# KMO_IO_MV2_91.net
KiCad netlist of a schematic drawn in EAGLE
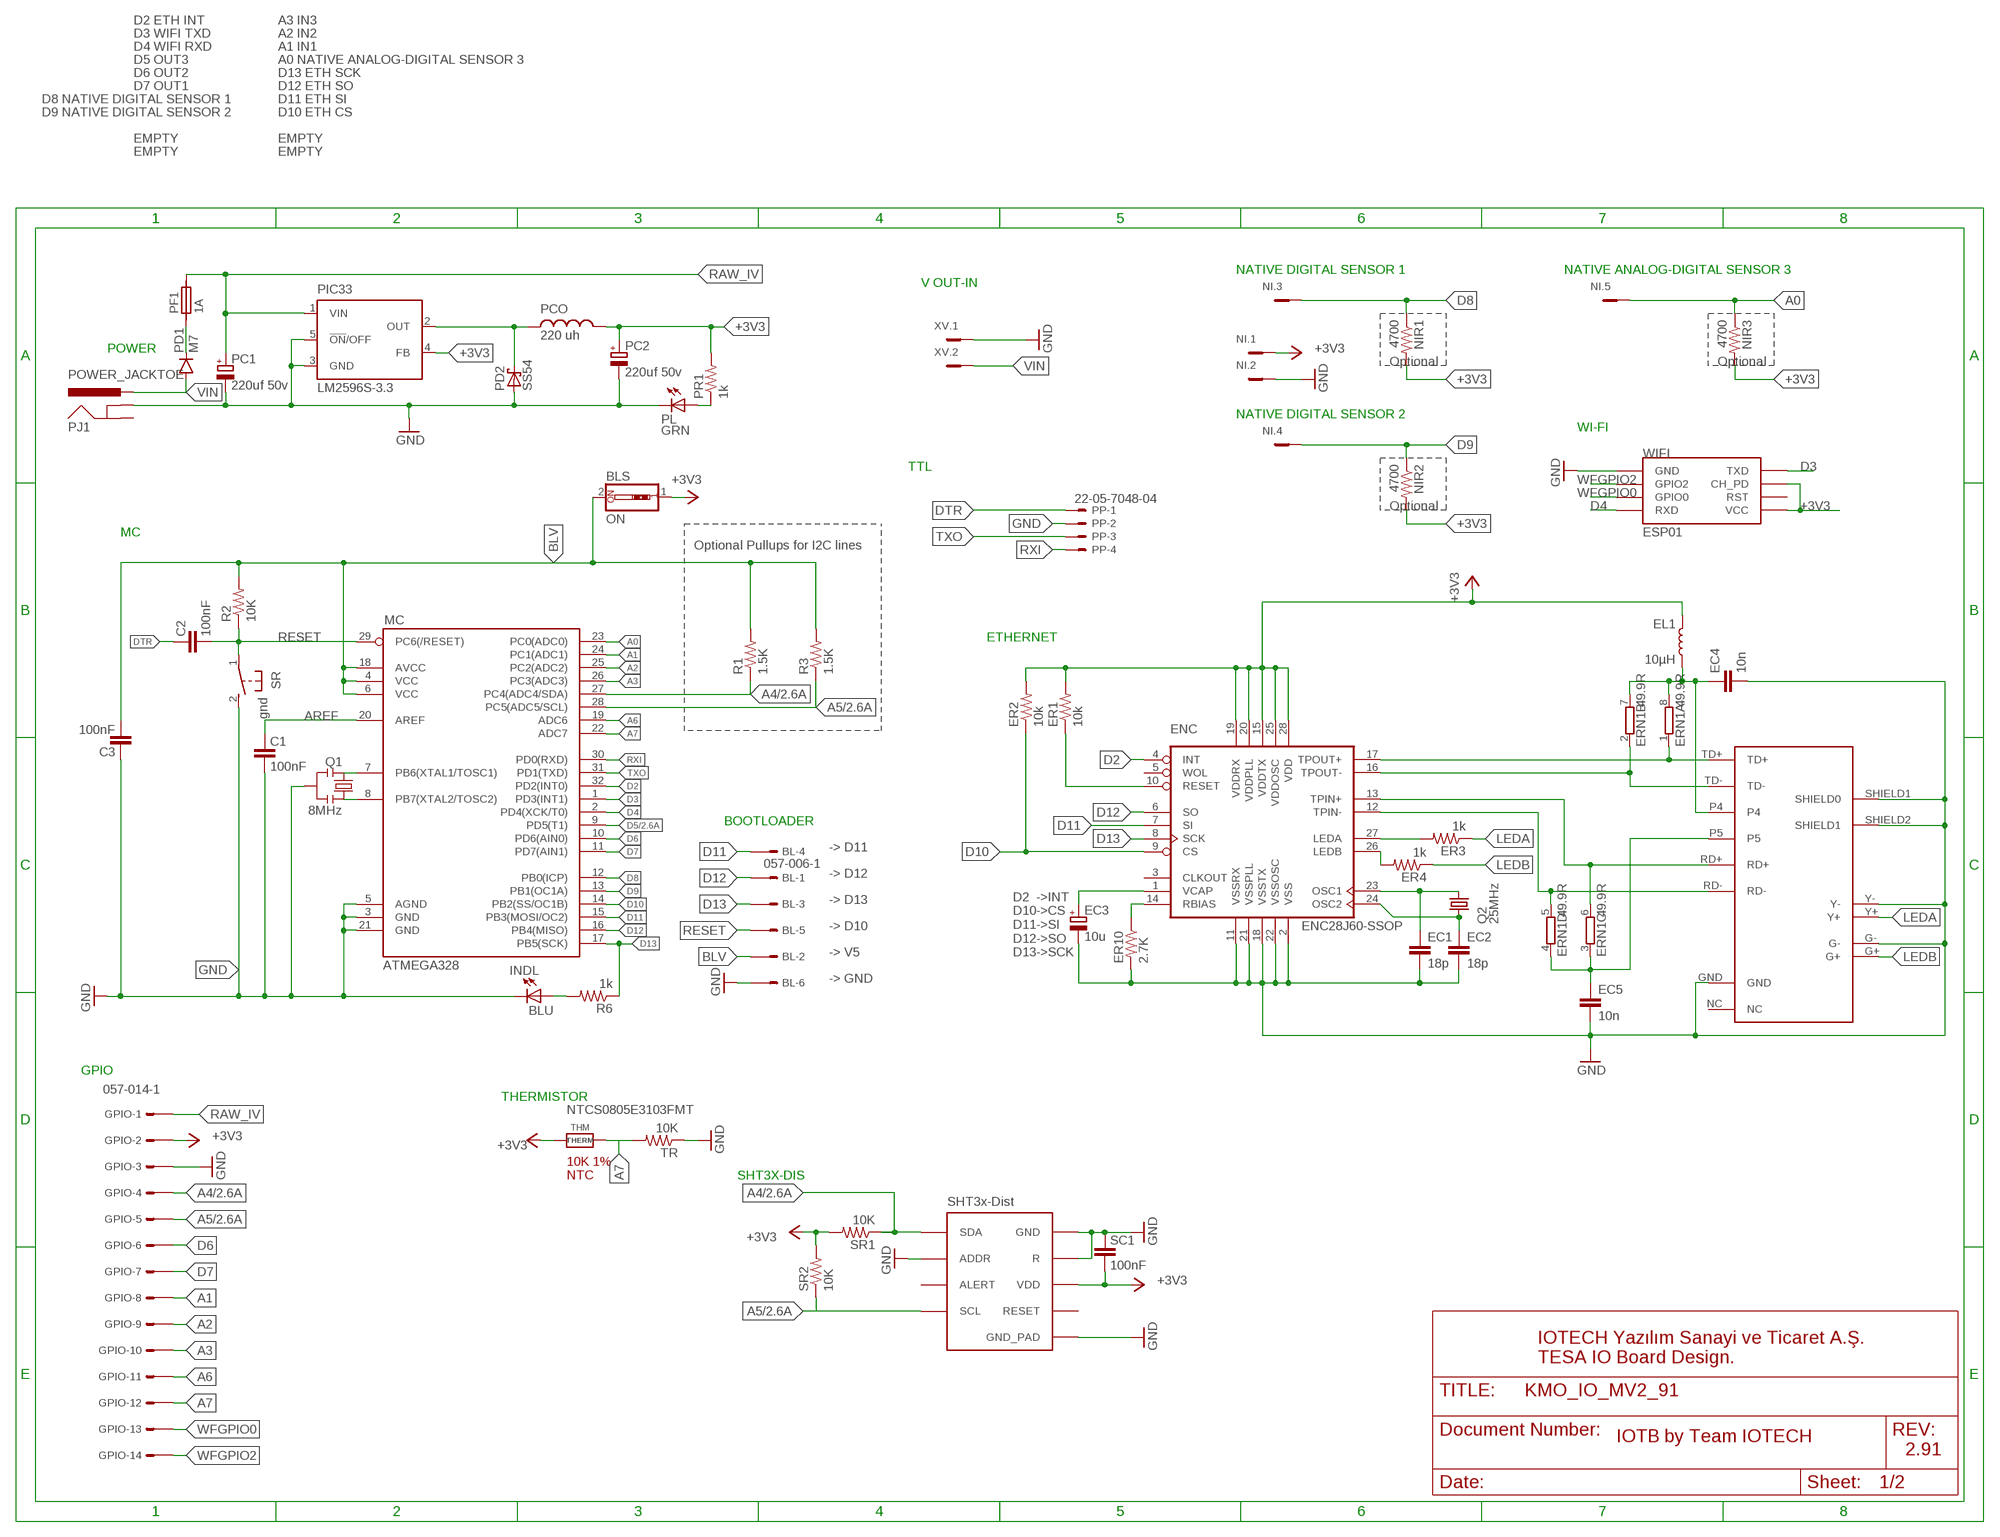
[diagram p0: schematic, sheet 1]
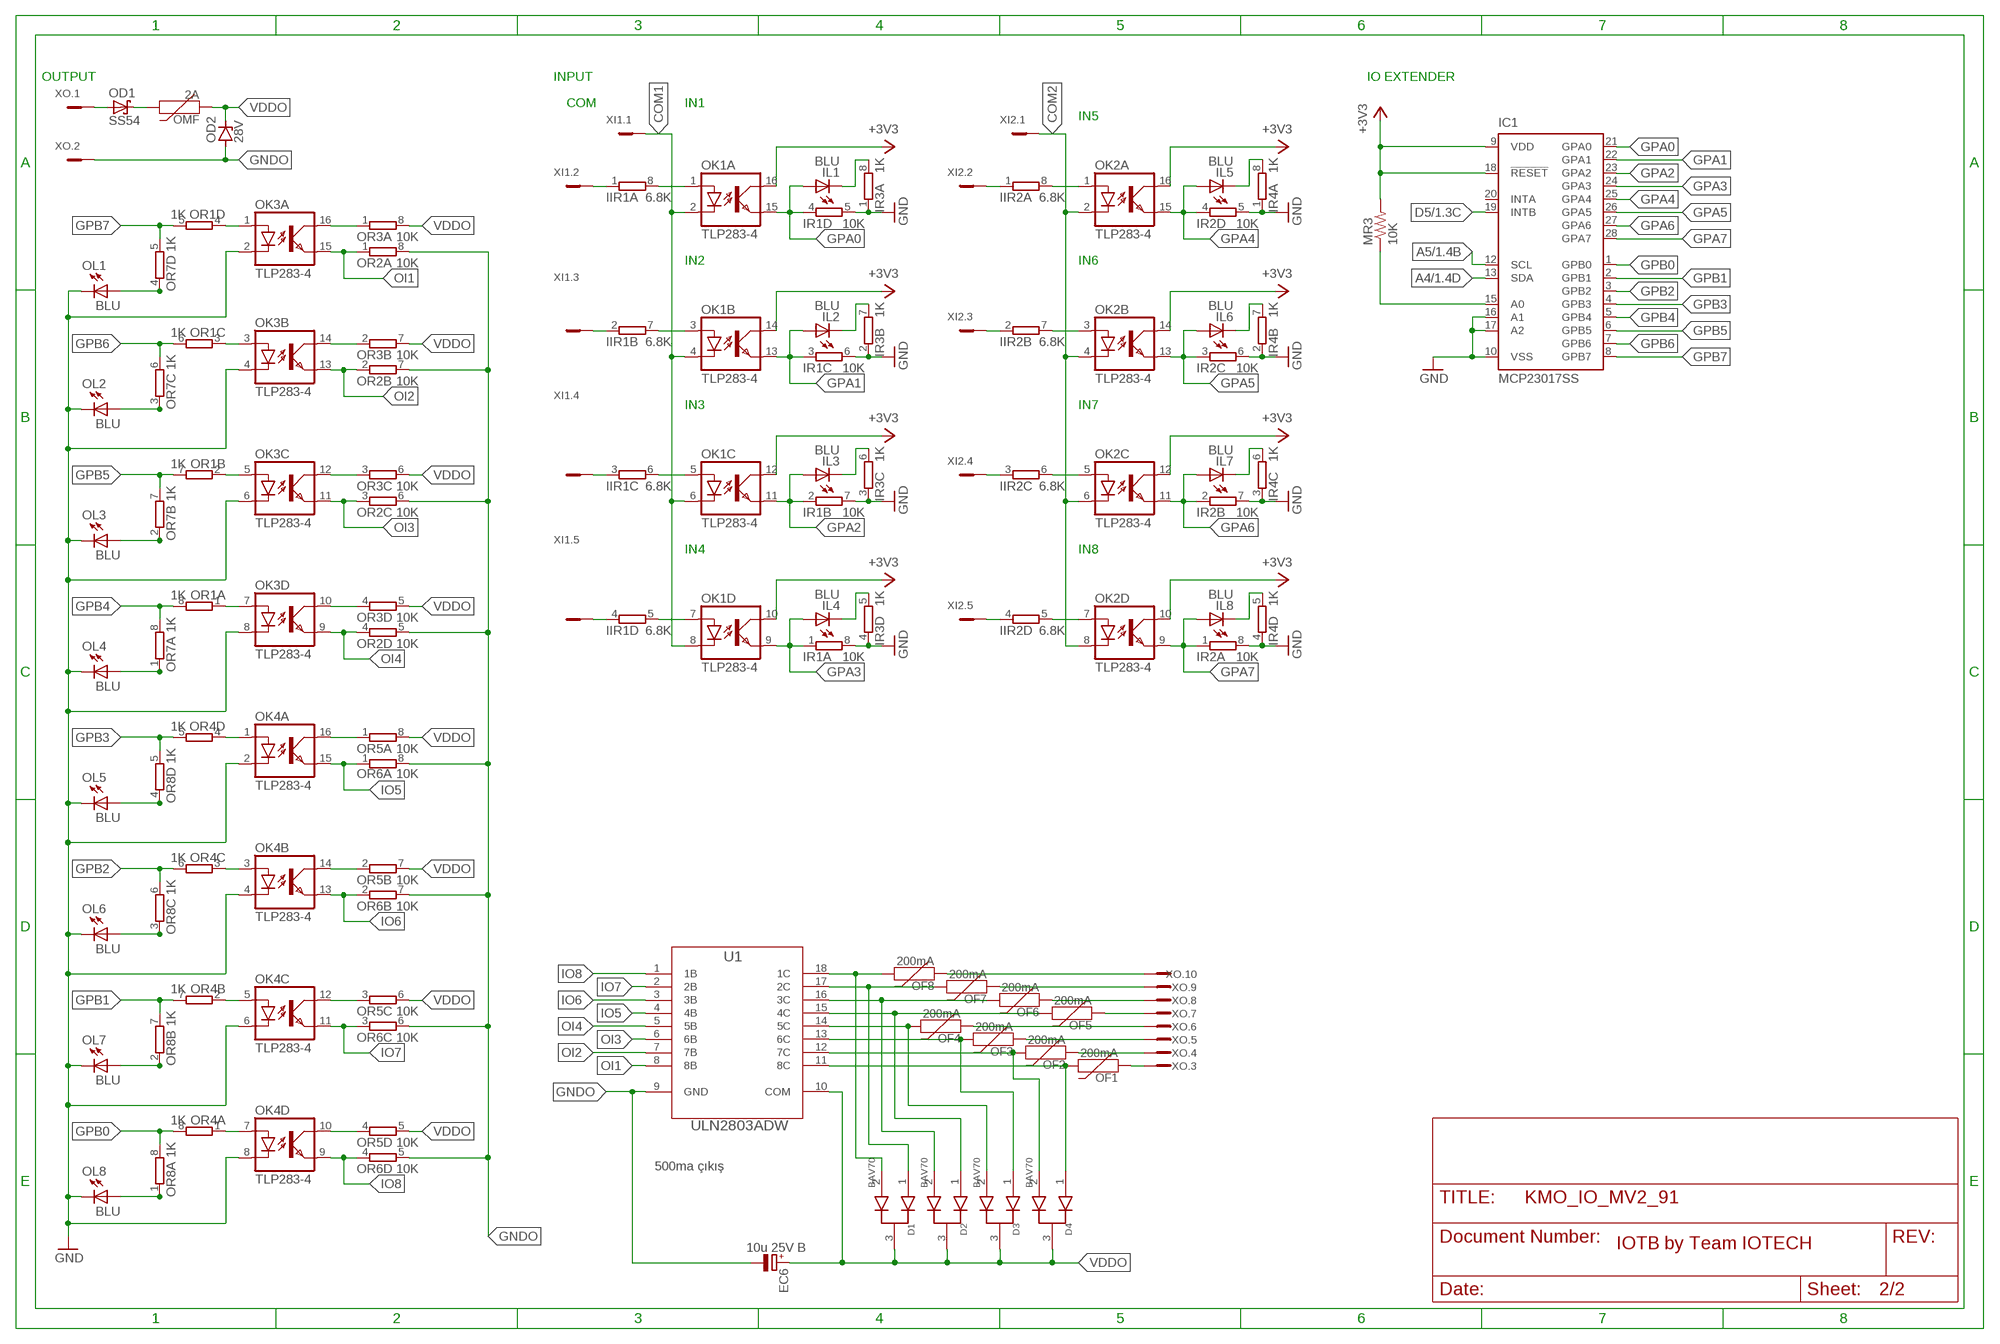
[diagram p1: schematic, sheet 2]

(export (version "E")
  (design (tool "Eeschema 10.0.6"))
  (components
    (comp (ref "D1")
      (value "BAV70")
      (footprint "eagle-import:SOT-23-3")
      (fields (field (name "MF") "Multicomp") (field (name "MP") "BAV70+"))
      (libsource (lib "eagle-import") (part "BAV70"))
    )
    (comp (ref "D2")
      (value "BAV70")
      (footprint "eagle-import:SOT-23-3")
      (fields (field (name "MF") "Multicomp") (field (name "MP") "BAV70+"))
      (libsource (lib "eagle-import") (part "BAV70"))
    )
    (comp (ref "D3")
      (value "BAV70")
      (footprint "eagle-import:SOT-23-3")
      (fields (field (name "MF") "Multicomp") (field (name "MP") "BAV70+"))
      (libsource (lib "eagle-import") (part "BAV70"))
    )
    (comp (ref "D4")
      (value "BAV70")
      (footprint "eagle-import:SOT-23-3")
      (fields (field (name "MF") "Multicomp") (field (name "MP") "BAV70+"))
      (libsource (lib "eagle-import") (part "BAV70"))
    )
    (comp (ref "EC6")
      (value "10u 25V B")
      (footprint "eagle-import:SMC_B")
      (libsource (lib "eagle-import") (part "CPOL-EUSMCB"))
    )
    (comp (ref "IC1")
      (value "MCP23017SS")
      (footprint "eagle-import:SSOP28")
      (fields (field (name "MF") "MICROCHIP") (field (name "MPN") "MCP23017-E/SS"))
      (libsource (lib "eagle-import") (part "MCP23017SS"))
    )
    (comp (ref "IIR1")
      (value "6.8K")
      (footprint "eagle-import:0603-ARV")
      (libsource (lib "eagle-import") (part "4R-N0603-ARV"))
    )
    (comp (ref "IIR2")
      (value "6.8K")
      (footprint "eagle-import:0603-ARV")
      (libsource (lib "eagle-import") (part "4R-N0603-ARV"))
    )
    (comp (ref "IL1")
      (value "BLU")
      (footprint "eagle-import:CHIP-LED0805")
      (libsource (lib "eagle-import") (part "LEDCHIP-LED0805"))
    )
    (comp (ref "IL2")
      (value "BLU")
      (footprint "eagle-import:CHIP-LED0805")
      (libsource (lib "eagle-import") (part "LEDCHIP-LED0805"))
    )
    (comp (ref "IL3")
      (value "BLU")
      (footprint "eagle-import:CHIP-LED0805")
      (libsource (lib "eagle-import") (part "LEDCHIP-LED0805"))
    )
    (comp (ref "IL4")
      (value "BLU")
      (footprint "eagle-import:CHIP-LED0805")
      (libsource (lib "eagle-import") (part "LEDCHIP-LED0805"))
    )
    (comp (ref "IL5")
      (value "BLU")
      (footprint "eagle-import:CHIP-LED0805")
      (libsource (lib "eagle-import") (part "LEDCHIP-LED0805"))
    )
    (comp (ref "IL6")
      (value "BLU")
      (footprint "eagle-import:CHIP-LED0805")
      (libsource (lib "eagle-import") (part "LEDCHIP-LED0805"))
    )
    (comp (ref "IL7")
      (value "BLU")
      (footprint "eagle-import:CHIP-LED0805")
      (libsource (lib "eagle-import") (part "LEDCHIP-LED0805"))
    )
    (comp (ref "IL8")
      (value "BLU")
      (footprint "eagle-import:CHIP-LED0805")
      (libsource (lib "eagle-import") (part "LEDCHIP-LED0805"))
    )
    (comp (ref "IR1")
      (value "10K")
      (footprint "eagle-import:0603-ARV")
      (libsource (lib "eagle-import") (part "4R-N0603-ARV"))
    )
    (comp (ref "IR2")
      (value "10K")
      (footprint "eagle-import:0603-ARV")
      (libsource (lib "eagle-import") (part "4R-N0603-ARV"))
    )
    (comp (ref "IR3")
      (value "1K")
      (footprint "eagle-import:0603-ARV")
      (libsource (lib "eagle-import") (part "4R-N0603-ARV"))
    )
    (comp (ref "IR4")
      (value "1K")
      (footprint "eagle-import:0603-ARV")
      (libsource (lib "eagle-import") (part "4R-N0603-ARV"))
    )
    (comp (ref "MR3")
      (value "10K")
      (footprint "eagle-import:0805")
      (libsource (lib "eagle-import") (part "RESISTOR0805-RES"))
    )
    (comp (ref "OD1")
      (value "SS54")
      (footprint "eagle-import:SMB")
      (libsource (lib "eagle-import") (part "SCHOTTKY-DIODESMD"))
    )
    (comp (ref "OD2")
      (value "28V")
      (footprint "eagle-import:SMB")
      (libsource (lib "eagle-import") (part "ZENER-DIODESMB"))
    )
    (comp (ref "OF1")
      (value "200mA")
      (footprint "eagle-import:1206")
      (libsource (lib "eagle-import") (part "PPTC_0.75A"))
    )
    (comp (ref "OF2")
      (value "200mA")
      (footprint "eagle-import:1206")
      (libsource (lib "eagle-import") (part "PPTC_0.75A"))
    )
    (comp (ref "OF3")
      (value "200mA")
      (footprint "eagle-import:1206")
      (libsource (lib "eagle-import") (part "PPTC_0.75A"))
    )
    (comp (ref "OF4")
      (value "200mA")
      (footprint "eagle-import:1206")
      (libsource (lib "eagle-import") (part "PPTC_0.75A"))
    )
    (comp (ref "OF5")
      (value "200mA")
      (footprint "eagle-import:1206")
      (libsource (lib "eagle-import") (part "PPTC_0.75A"))
    )
    (comp (ref "OF6")
      (value "200mA")
      (footprint "eagle-import:1206")
      (libsource (lib "eagle-import") (part "PPTC_0.75A"))
    )
    (comp (ref "OF7")
      (value "200mA")
      (footprint "eagle-import:1206")
      (libsource (lib "eagle-import") (part "PPTC_0.75A"))
    )
    (comp (ref "OF8")
      (value "200mA")
      (footprint "eagle-import:1206")
      (libsource (lib "eagle-import") (part "PPTC_0.75A"))
    )
    (comp (ref "OK1")
      (value "TLP283-4")
      (footprint "eagle-import:MINI-FLAT-16")
      (fields (field (name "SPICEPREFIX") "O"))
      (libsource (lib "eagle-import") (part "TLP283-4"))
    )
    (comp (ref "OK2")
      (value "TLP283-4")
      (footprint "eagle-import:MINI-FLAT-16")
      (fields (field (name "SPICEPREFIX") "O"))
      (libsource (lib "eagle-import") (part "TLP283-4"))
    )
    (comp (ref "OK3")
      (value "TLP283-4")
      (footprint "eagle-import:MINI-FLAT-16")
      (libsource (lib "eagle-import") (part "TLP283-4"))
    )
    (comp (ref "OK4")
      (value "TLP283-4")
      (footprint "eagle-import:MINI-FLAT-16")
      (libsource (lib "eagle-import") (part "TLP283-4"))
    )
    (comp (ref "OL1")
      (value "BLU")
      (footprint "eagle-import:CHIP-LED0805")
      (libsource (lib "eagle-import") (part "LEDCHIP-LED0805"))
    )
    (comp (ref "OL2")
      (value "BLU")
      (footprint "eagle-import:CHIP-LED0805")
      (libsource (lib "eagle-import") (part "LEDCHIP-LED0805"))
    )
    (comp (ref "OL3")
      (value "BLU")
      (footprint "eagle-import:CHIP-LED0805")
      (libsource (lib "eagle-import") (part "LEDCHIP-LED0805"))
    )
    (comp (ref "OL4")
      (value "BLU")
      (footprint "eagle-import:CHIP-LED0805")
      (libsource (lib "eagle-import") (part "LEDCHIP-LED0805"))
    )
    (comp (ref "OL5")
      (value "BLU")
      (footprint "eagle-import:CHIP-LED0805")
      (libsource (lib "eagle-import") (part "LEDCHIP-LED0805"))
    )
    (comp (ref "OL6")
      (value "BLU")
      (footprint "eagle-import:CHIP-LED0805")
      (libsource (lib "eagle-import") (part "LEDCHIP-LED0805"))
    )
    (comp (ref "OL7")
      (value "BLU")
      (footprint "eagle-import:CHIP-LED0805")
      (libsource (lib "eagle-import") (part "LEDCHIP-LED0805"))
    )
    (comp (ref "OL8")
      (value "BLU")
      (footprint "eagle-import:CHIP-LED0805")
      (libsource (lib "eagle-import") (part "LEDCHIP-LED0805"))
    )
    (comp (ref "OMF")
      (value "2A")
      (footprint "eagle-import:1206")
      (libsource (lib "eagle-import") (part "PPTC_0.75A"))
    )
    (comp (ref "OR1")
      (value "1K")
      (footprint "eagle-import:0603-ARV")
      (libsource (lib "eagle-import") (part "4R-N0603-ARV"))
    )
    (comp (ref "OR2")
      (value "10K")
      (footprint "eagle-import:0603-ARV")
      (libsource (lib "eagle-import") (part "4R-N0603-ARV"))
    )
    (comp (ref "OR3")
      (value "10K")
      (footprint "eagle-import:0603-ARV")
      (libsource (lib "eagle-import") (part "4R-N0603-ARV"))
    )
    (comp (ref "OR4")
      (value "1K")
      (footprint "eagle-import:0603-ARV")
      (libsource (lib "eagle-import") (part "4R-N0603-ARV"))
    )
    (comp (ref "OR5")
      (value "10K")
      (footprint "eagle-import:0603-ARV")
      (libsource (lib "eagle-import") (part "4R-N0603-ARV"))
    )
    (comp (ref "OR6")
      (value "10K")
      (footprint "eagle-import:0603-ARV")
      (libsource (lib "eagle-import") (part "4R-N0603-ARV"))
    )
    (comp (ref "OR7")
      (value "1K")
      (footprint "eagle-import:0603-ARV")
      (libsource (lib "eagle-import") (part "4R-N0603-ARV"))
    )
    (comp (ref "OR8")
      (value "1K")
      (footprint "eagle-import:0603-ARV")
      (libsource (lib "eagle-import") (part "4R-N0603-ARV"))
    )
    (comp (ref "U1")
      (value "ULN2803ADW")
      (footprint "eagle-import:SOIC127P1030X265-18N")
      (libsource (lib "eagle-import") (part "ULN2803ADW"))
    )
    (comp (ref "XI1")
      (value "MC5")
      (footprint "eagle-import:MC5")
      (libsource (lib "eagle-import") (part "MC5"))
    )
    (comp (ref "XI2")
      (value "MC5")
      (footprint "eagle-import:MC5")
      (libsource (lib "eagle-import") (part "MC5"))
    )
    (comp (ref "XO")
      (value "MC10")
      (footprint "eagle-import:MC10")
      (libsource (lib "eagle-import") (part "MC10"))
    )
    (comp (ref "BL")
      (value "057-006-1")
      (footprint "eagle-import:057-006-1")
      (libsource (lib "eagle-import") (part "057-006-1"))
    )
    (comp (ref "BLS")
      (value "ON")
      (footprint "eagle-import:EDG-01")
      (libsource (lib "eagle-import") (part "SW_DIP-1"))
    )
    (comp (ref "C1")
      (value "100nF")
      (footprint "eagle-import:0805")
      (libsource (lib "eagle-import") (part "CAP0805"))
    )
    (comp (ref "C2")
      (value "100nF")
      (footprint "eagle-import:0805")
      (libsource (lib "eagle-import") (part "CAP0805"))
    )
    (comp (ref "C3")
      (value "100nF")
      (footprint "eagle-import:0805")
      (libsource (lib "eagle-import") (part "CAP0805"))
    )
    (comp (ref "EC1")
      (value "18p")
      (footprint "eagle-import:0805")
      (libsource (lib "eagle-import") (part "CAP0805"))
    )
    (comp (ref "EC2")
      (value "18p")
      (footprint "eagle-import:0805")
      (libsource (lib "eagle-import") (part "CAP0805"))
    )
    (comp (ref "EC3")
      (value "10u")
      (footprint "eagle-import:CT3216")
      (libsource (lib "eagle-import") (part "CPOL-EUCT3216"))
    )
    (comp (ref "EC4")
      (value "10n")
      (footprint "eagle-import:0805")
      (libsource (lib "eagle-import") (part "CAP0805"))
    )
    (comp (ref "EC5")
      (value "10n")
      (footprint "eagle-import:0805")
      (libsource (lib "eagle-import") (part "CAP0805"))
    )
    (comp (ref "EL1")
      (value "10µH")
      (footprint "eagle-import:0805")
      (libsource (lib "eagle-import") (part "INDUCTOR-0805-3.3UH"))
    )
    (comp (ref "ENC")
      (value "ENC28J60-SSOP")
      (footprint "eagle-import:SSOP28")
      (libsource (lib "eagle-import") (part "ENC28J60-SSOP"))
    )
    (comp (ref "ER1")
      (value "10k")
      (footprint "eagle-import:0805")
      (libsource (lib "eagle-import") (part "RESISTOR0805-RES"))
    )
    (comp (ref "ER2")
      (value "10k")
      (footprint "eagle-import:0805")
      (libsource (lib "eagle-import") (part "RESISTOR0805-RES"))
    )
    (comp (ref "ER3")
      (value "1k")
      (footprint "eagle-import:0805")
      (libsource (lib "eagle-import") (part "RESISTOR0805-RES"))
    )
    (comp (ref "ER4")
      (value "1k")
      (footprint "eagle-import:0805")
      (libsource (lib "eagle-import") (part "RESISTOR0805-RES"))
    )
    (comp (ref "ER10")
      (value "2.7K")
      (footprint "eagle-import:0805")
      (libsource (lib "eagle-import") (part "RESISTOR0805-RES"))
    )
    (comp (ref "ERN1")
      (value "49.9R")
      (footprint "eagle-import:0603-ARV")
      (libsource (lib "eagle-import") (part "4R-N0603-ARV"))
    )
    (comp (ref "GPIO")
      (value "057-014-1")
      (footprint "eagle-import:057-014-1")
      (libsource (lib "eagle-import") (part "057-014-1"))
    )
    (comp (ref "INDL")
      (value "BLU")
      (footprint "eagle-import:CHIP-LED0805")
      (libsource (lib "eagle-import") (part "LEDCHIP-LED0805"))
    )
    (comp (ref "MC")
      (value "ATMEGA328")
      (footprint "eagle-import:TQFP32-08")
      (libsource (lib "eagle-import") (part "ATMEGA168"))
    )
    (comp (ref "NI")
      (value "MC5")
      (footprint "eagle-import:MC5")
      (libsource (lib "eagle-import") (part "MC5"))
    )
    (comp (ref "NIR1")
      (value "4700")
      (footprint "eagle-import:0805")
      (libsource (lib "eagle-import") (part "RESISTOR0805-RES"))
    )
    (comp (ref "NIR2")
      (value "4700")
      (footprint "eagle-import:0805")
      (libsource (lib "eagle-import") (part "RESISTOR0805-RES"))
    )
    (comp (ref "NIR3")
      (value "4700")
      (footprint "eagle-import:0805")
      (libsource (lib "eagle-import") (part "RESISTOR0805-RES"))
    )
    (comp (ref "PC1")
      (value "220uf 50v")
      (footprint "eagle-import:140CLH-1010")
      (libsource (lib "eagle-import") (part "CPOL-EU140CLH-1010"))
    )
    (comp (ref "PC2")
      (value "220uf 50v")
      (footprint "eagle-import:140CLH-1010")
      (libsource (lib "eagle-import") (part "CPOL-EU140CLH-1010"))
    )
    (comp (ref "PCO")
      (value "220 uh")
      (footprint "eagle-import:MSS1260")
      (libsource (lib "eagle-import") (part "MSS1260"))
    )
    (comp (ref "PD1")
      (value "M7")
      (footprint "eagle-import:SMA-DIODE")
      (libsource (lib "eagle-import") (part "DIODESMA"))
    )
    (comp (ref "PD2")
      (value "SS54")
      (footprint "eagle-import:SMB")
      (libsource (lib "eagle-import") (part "SCHOTTKY-DIODESMD"))
    )
    (comp (ref "PF1")
      (value "1A")
      (footprint "eagle-import:1820")
      (libsource (lib "eagle-import") (part "SIBA194600"))
    )
    (comp (ref "PIC33")
      (value "LM2596S-3.3")
      (footprint "eagle-import:TO263-5")
      (fields
        (field (name "MF") "NATIONAL SEMICONDUCTOR")
        (field (name "MPN") "LM2596S-ADJ/NOPB")
        (field (name "SPICEPREFIX") "X")
      )
      (libsource (lib "eagle-import") (part "LM2596S"))
    )
    (comp (ref "PJ1")
      (value "POWER_JACKTOE")
      (footprint "eagle-import:POWER_JACK_SMD_OVERPASTE_TOE")
      (libsource (lib "eagle-import") (part "POWER_JACKTOE"))
    )
    (comp (ref "PL")
      (value "GRN")
      (footprint "eagle-import:CHIP-LED0805")
      (libsource (lib "eagle-import") (part "LEDCHIP-LED0805"))
    )
    (comp (ref "PP")
      (value "22-05-7048-04")
      (footprint "eagle-import:7395-04")
      (fields (field (name "MF") "MOLEX"))
      (libsource (lib "eagle-import") (part "22-?-0405-7048"))
    )
    (comp (ref "PR1")
      (value "1k")
      (footprint "eagle-import:0805")
      (libsource (lib "eagle-import") (part "RESISTOR0805-RES"))
    )
    (comp (ref "Q1")
      (value "8MHz")
      (footprint "eagle-import:RESONATOR-SMD-1_1")
      (libsource (lib "eagle-import") (part "RESONATOR1{colon}1"))
    )
    (comp (ref "Q2")
      (value "25MHz")
      (footprint "eagle-import:5.0X3.2_2")
      (libsource (lib "eagle-import") (part "KX-9B"))
    )
    (comp (ref "R1")
      (value "1.5K")
      (footprint "eagle-import:0805")
      (libsource (lib "eagle-import") (part "RESISTOR0805-RES"))
    )
    (comp (ref "R2")
      (value "10K")
      (footprint "eagle-import:0805")
      (libsource (lib "eagle-import") (part "RESISTOR0805-RES"))
    )
    (comp (ref "R3")
      (value "1.5K")
      (footprint "eagle-import:0805")
      (libsource (lib "eagle-import") (part "RESISTOR0805-RES"))
    )
    (comp (ref "R6")
      (value "1k")
      (footprint "eagle-import:0805")
      (libsource (lib "eagle-import") (part "RESISTOR0805-RES"))
    )
    (comp (ref "SC1")
      (value "100nF")
      (footprint "eagle-import:0805")
      (libsource (lib "eagle-import") (part "CAP0805"))
    )
    (comp (ref "SHT")
      (value "SHT3X")
      (footprint "eagle-import:SHT3X")
      (libsource (lib "eagle-import") (part "SHT3X"))
    )
    (comp (ref "SR")
      (value "gnd")
      (footprint "eagle-import:B3F-31XX")
      (fields (field (name "MPN") "B3F-3100"))
      (libsource (lib "eagle-import") (part "31-XX"))
    )
    (comp (ref "SR1")
      (value "10K")
      (footprint "eagle-import:0805")
      (libsource (lib "eagle-import") (part "RESISTOR0805-RES"))
    )
    (comp (ref "SR2")
      (value "10K")
      (footprint "eagle-import:0805")
      (libsource (lib "eagle-import") (part "RESISTOR0805-RES"))
    )
    (comp (ref "THM")
      (value "THERM")
      (footprint "eagle-import:MICROBUILDER_0805_NOTHERMALS")
      (libsource (lib "eagle-import") (part "MICROBUILDER_RESISTOR0805_NOTHERMALS"))
    )
    (comp (ref "TR")
      (value "10K")
      (footprint "eagle-import:0805")
      (libsource (lib "eagle-import") (part "RESISTOR0805-RES"))
    )
    (comp (ref "U$2")
      (value "HR911105A")
      (footprint "eagle-import:RJ45")
      (libsource (lib "eagle-import") (part "HR911105A"))
    )
    (comp (ref "WIFI")
      (value "ESP01")
      (footprint "eagle-import:ESP01")
      (libsource (lib "eagle-import") (part "ESP01"))
    )
    (comp (ref "XV")
      (value "MC2")
      (footprint "eagle-import:MC2")
      (libsource (lib "eagle-import") (part "MC2"))
    )
  )
  (nets
    (net (code "1") (name "+3V3") (class "Default")
      (node (ref "BLS") (pin "1") (pinfunction "1_1") (pintype "passive"))
      (node (ref "EL1") (pin "1") (pinfunction "1_1") (pintype "passive"))
      (node (ref "ENC") (pin "15") (pinfunction "VDDTX_15") (pintype "power_in"))
      (node (ref "ENC") (pin "19") (pinfunction "VDDRX_19") (pintype "power_in"))
      (node (ref "ENC") (pin "20") (pinfunction "VDDPLL_20") (pintype "power_in"))
      (node (ref "ENC") (pin "25") (pinfunction "VDDOSC_25") (pintype "power_in"))
      (node (ref "ENC") (pin "28") (pinfunction "VDD_28") (pintype "power_in"))
      (node (ref "ER1") (pin "2") (pinfunction "2_2") (pintype "passive"))
      (node (ref "ER2") (pin "2") (pinfunction "2_2") (pintype "passive"))
      (node (ref "GPIO") (pin "2") (pinfunction "S_2") (pintype "passive"))
      (node (ref "IC1") (pin "18") (pinfunction "~{RESET}_18") (pintype "input"))
      (node (ref "IC1") (pin "9") (pinfunction "VDD_9") (pintype "power_in"))
      (node (ref "MR3") (pin "2") (pinfunction "2_2") (pintype "passive"))
      (node (ref "NI") (pin "1") (pinfunction "SK_1") (pintype "passive"))
      (node (ref "NIR1") (pin "2") (pinfunction "2_2") (pintype "passive"))
      (node (ref "NIR2") (pin "2") (pinfunction "2_2") (pintype "passive"))
      (node (ref "NIR3") (pin "2") (pinfunction "2_2") (pintype "passive"))
      (node (ref "OK1") (pin "10") (pinfunction "COL_10") (pintype "passive"))
      (node (ref "OK1") (pin "12") (pinfunction "COL_12") (pintype "passive"))
      (node (ref "OK1") (pin "14") (pinfunction "COL_14") (pintype "passive"))
      (node (ref "OK1") (pin "16") (pinfunction "COL_16") (pintype "passive"))
      (node (ref "OK2") (pin "10") (pinfunction "COL_10") (pintype "passive"))
      (node (ref "OK2") (pin "12") (pinfunction "COL_12") (pintype "passive"))
      (node (ref "OK2") (pin "14") (pinfunction "COL_14") (pintype "passive"))
      (node (ref "OK2") (pin "16") (pinfunction "COL_16") (pintype "passive"))
      (node (ref "PC2") (pin "+") (pinfunction "+_+") (pintype "passive"))
      (node (ref "PCO") (pin "P$1") (pinfunction "P$1_P$1") (pintype "passive"))
      (node (ref "PIC33") (pin "4") (pinfunction "FB_4") (pintype "input"))
      (node (ref "PR1") (pin "2") (pinfunction "2_2") (pintype "passive"))
      (node (ref "SC1") (pin "1") (pinfunction "1_1") (pintype "passive"))
      (node (ref "SHT") (pin "VDD") (pinfunction "VDD_VDD") (pintype "bidirectional"))
      (node (ref "SR1") (pin "2") (pinfunction "2_2") (pintype "passive"))
      (node (ref "SR2") (pin "2") (pinfunction "2_2") (pintype "passive"))
      (node (ref "THM") (pin "1") (pinfunction "1_1") (pintype "passive"))
      (node (ref "WIFI") (pin "CH_PD") (pinfunction "CH_PD_CH_PD") (pintype "bidirectional"))
      (node (ref "WIFI") (pin "VCC") (pinfunction "VCC_VCC") (pintype "bidirectional"))
    )
    (net (code "2") (name "A0") (class "Default")
      (node (ref "MC") (pin "23") (pinfunction "PC0(ADC0)_23") (pintype "bidirectional"))
      (node (ref "NI") (pin "5") (pinfunction "SK_5") (pintype "passive"))
      (node (ref "NIR3") (pin "1") (pinfunction "1_1") (pintype "passive"))
    )
    (net (code "3") (name "A1") (class "Default")
      (node (ref "GPIO") (pin "8") (pinfunction "S_8") (pintype "passive"))
      (node (ref "MC") (pin "24") (pinfunction "PC1(ADC1)_24") (pintype "bidirectional"))
    )
    (net (code "4") (name "A2") (class "Default")
      (node (ref "GPIO") (pin "9") (pinfunction "S_9") (pintype "passive"))
      (node (ref "MC") (pin "25") (pinfunction "PC2(ADC2)_25") (pintype "bidirectional"))
    )
    (net (code "5") (name "A3") (class "Default")
      (node (ref "GPIO") (pin "10") (pinfunction "S_10") (pintype "passive"))
      (node (ref "MC") (pin "26") (pinfunction "PC3(ADC3)_26") (pintype "bidirectional"))
    )
    (net (code "6") (name "A4") (class "Default")
      (node (ref "GPIO") (pin "4") (pinfunction "S_4") (pintype "passive"))
      (node (ref "IC1") (pin "13") (pinfunction "SDA_13") (pintype "bidirectional"))
      (node (ref "MC") (pin "27") (pinfunction "PC4(ADC4/SDA)_27") (pintype "bidirectional"))
      (node (ref "R1") (pin "1") (pinfunction "1_1") (pintype "passive"))
      (node (ref "SHT") (pin "SDA") (pinfunction "SDA_SDA") (pintype "bidirectional"))
      (node (ref "SR1") (pin "1") (pinfunction "1_1") (pintype "passive"))
    )
    (net (code "7") (name "A5") (class "Default")
      (node (ref "GPIO") (pin "5") (pinfunction "S_5") (pintype "passive"))
      (node (ref "IC1") (pin "12") (pinfunction "SCL_12") (pintype "input"))
      (node (ref "MC") (pin "28") (pinfunction "PC5(ADC5/SCL)_28") (pintype "bidirectional"))
      (node (ref "R3") (pin "1") (pinfunction "1_1") (pintype "passive"))
      (node (ref "SHT") (pin "SCL") (pinfunction "SCL_SCL") (pintype "bidirectional"))
      (node (ref "SR2") (pin "1") (pinfunction "1_1") (pintype "passive"))
    )
    (net (code "8") (name "A6") (class "Default")
      (node (ref "GPIO") (pin "11") (pinfunction "S_11") (pintype "passive"))
      (node (ref "MC") (pin "19") (pinfunction "ADC6_19") (pintype "bidirectional"))
    )
    (net (code "9") (name "A7") (class "Default")
      (node (ref "GPIO") (pin "12") (pinfunction "S_12") (pintype "passive"))
      (node (ref "MC") (pin "22") (pinfunction "ADC7_22") (pintype "bidirectional"))
      (node (ref "THM") (pin "2") (pinfunction "2_2") (pintype "passive"))
      (node (ref "TR") (pin "2") (pinfunction "2_2") (pintype "passive"))
    )
    (net (code "10") (name "AREF") (class "Default")
      (node (ref "C1") (pin "2") (pinfunction "2_2") (pintype "passive"))
      (node (ref "MC") (pin "20") (pinfunction "AREF_20") (pintype "bidirectional"))
    )
    (net (code "11") (name "BLV") (class "Default")
      (node (ref "BL") (pin "2") (pinfunction "S_2") (pintype "passive"))
      (node (ref "BLS") (pin "2") (pinfunction "2_2") (pintype "passive"))
      (node (ref "C3") (pin "1") (pinfunction "1_1") (pintype "passive"))
      (node (ref "MC") (pin "18") (pinfunction "AVCC_18") (pintype "bidirectional"))
      (node (ref "MC") (pin "4") (pinfunction "VCC_4") (pintype "bidirectional"))
      (node (ref "MC") (pin "6") (pinfunction "VCC_6") (pintype "bidirectional"))
      (node (ref "R1") (pin "2") (pinfunction "2_2") (pintype "passive"))
      (node (ref "R2") (pin "2") (pinfunction "2_2") (pintype "passive"))
      (node (ref "R3") (pin "2") (pinfunction "2_2") (pintype "passive"))
    )
    (net (code "12") (name "COM1") (class "Default")
      (node (ref "OK1") (pin "2") (pinfunction "C_2") (pintype "passive"))
      (node (ref "OK1") (pin "4") (pinfunction "C_4") (pintype "passive"))
      (node (ref "OK1") (pin "6") (pinfunction "C_6") (pintype "passive"))
      (node (ref "OK1") (pin "8") (pinfunction "C_8") (pintype "passive"))
      (node (ref "XI1") (pin "1") (pinfunction "SK_1") (pintype "passive"))
    )
    (net (code "13") (name "COM2") (class "Default")
      (node (ref "OK2") (pin "2") (pinfunction "C_2") (pintype "passive"))
      (node (ref "OK2") (pin "4") (pinfunction "C_4") (pintype "passive"))
      (node (ref "OK2") (pin "6") (pinfunction "C_6") (pintype "passive"))
      (node (ref "OK2") (pin "8") (pinfunction "C_8") (pintype "passive"))
      (node (ref "XI2") (pin "1") (pinfunction "SK_1") (pintype "passive"))
    )
    (net (code "14") (name "D2") (class "Default")
      (node (ref "ENC") (pin "4") (pinfunction "INT_4") (pintype "output"))
      (node (ref "MC") (pin "32") (pinfunction "PD2(INT0)_32") (pintype "bidirectional"))
    )
    (net (code "15") (name "D3") (class "Default")
      (node (ref "MC") (pin "1") (pinfunction "PD3(INT1)_1") (pintype "bidirectional"))
      (node (ref "WIFI") (pin "TX") (pinfunction "TXD_TX") (pintype "bidirectional"))
    )
    (net (code "16") (name "D4") (class "Default")
      (node (ref "MC") (pin "2") (pinfunction "PD4(XCK/T0)_2") (pintype "bidirectional"))
      (node (ref "WIFI") (pin "RX") (pinfunction "RXD_RX") (pintype "bidirectional"))
    )
    (net (code "17") (name "D5") (class "Default")
      (node (ref "IC1") (pin "19") (pinfunction "INTB_19") (pintype "output"))
      (node (ref "MC") (pin "9") (pinfunction "PD5(T1)_9") (pintype "bidirectional"))
    )
    (net (code "18") (name "D6") (class "Default")
      (node (ref "GPIO") (pin "6") (pinfunction "S_6") (pintype "passive"))
      (node (ref "MC") (pin "10") (pinfunction "PD6(AIN0)_10") (pintype "bidirectional"))
    )
    (net (code "19") (name "D7") (class "Default")
      (node (ref "GPIO") (pin "7") (pinfunction "S_7") (pintype "passive"))
      (node (ref "MC") (pin "11") (pinfunction "PD7(AIN1)_11") (pintype "bidirectional"))
    )
    (net (code "20") (name "D8") (class "Default")
      (node (ref "MC") (pin "12") (pinfunction "PB0(ICP)_12") (pintype "bidirectional"))
      (node (ref "NI") (pin "3") (pinfunction "SK_3") (pintype "passive"))
      (node (ref "NIR1") (pin "1") (pinfunction "1_1") (pintype "passive"))
    )
    (net (code "21") (name "D9") (class "Default")
      (node (ref "MC") (pin "13") (pinfunction "PB1(OC1A)_13") (pintype "bidirectional"))
      (node (ref "NI") (pin "4") (pinfunction "SK_4") (pintype "passive"))
      (node (ref "NIR2") (pin "1") (pinfunction "1_1") (pintype "passive"))
    )
    (net (code "22") (name "D10") (class "Default")
      (node (ref "ENC") (pin "9") (pinfunction "CS_9") (pintype "input"))
      (node (ref "ER2") (pin "1") (pinfunction "1_1") (pintype "passive"))
      (node (ref "MC") (pin "14") (pinfunction "PB2(SS/OC1B)_14") (pintype "bidirectional"))
    )
    (net (code "23") (name "D11") (class "Default")
      (node (ref "BL") (pin "4") (pinfunction "S_4") (pintype "passive"))
      (node (ref "ENC") (pin "7") (pinfunction "SI_7") (pintype "input"))
      (node (ref "MC") (pin "15") (pinfunction "PB3(MOSI/OC2)_15") (pintype "bidirectional"))
    )
    (net (code "24") (name "D12") (class "Default")
      (node (ref "BL") (pin "1") (pinfunction "S_1") (pintype "passive"))
      (node (ref "ENC") (pin "6") (pinfunction "SO_6") (pintype "output"))
      (node (ref "MC") (pin "16") (pinfunction "PB4(MISO)_16") (pintype "bidirectional"))
    )
    (net (code "25") (name "D13") (class "Default")
      (node (ref "BL") (pin "3") (pinfunction "S_3") (pintype "passive"))
      (node (ref "ENC") (pin "8") (pinfunction "SCK_8") (pintype "input"))
      (node (ref "MC") (pin "17") (pinfunction "PB5(SCK)_17") (pintype "bidirectional"))
      (node (ref "R6") (pin "1") (pinfunction "1_1") (pintype "passive"))
    )
    (net (code "26") (name "DTR") (class "Default")
      (node (ref "C2") (pin "2") (pinfunction "2_2") (pintype "passive"))
      (node (ref "PP") (pin "1") (pinfunction "S_1") (pintype "passive"))
    )
    (net (code "27") (name "GND") (class "Default")
      (node (ref "BL") (pin "6") (pinfunction "S_6") (pintype "passive"))
      (node (ref "C1") (pin "1") (pinfunction "1_1") (pintype "passive"))
      (node (ref "C3") (pin "2") (pinfunction "2_2") (pintype "passive"))
      (node (ref "EC1") (pin "2") (pinfunction "2_2") (pintype "passive"))
      (node (ref "EC2") (pin "2") (pinfunction "2_2") (pintype "passive"))
      (node (ref "EC3") (pin "-") (pinfunction "-_-") (pintype "passive"))
      (node (ref "EC4") (pin "2") (pinfunction "2_2") (pintype "passive"))
      (node (ref "EC5") (pin "2") (pinfunction "2_2") (pintype "passive"))
      (node (ref "ENC") (pin "11") (pinfunction "VSSRX_11") (pintype "power_in"))
      (node (ref "ENC") (pin "18") (pinfunction "VSSTX_18") (pintype "power_in"))
      (node (ref "ENC") (pin "2") (pinfunction "VSS_2") (pintype "power_in"))
      (node (ref "ENC") (pin "21") (pinfunction "VSSPLL_21") (pintype "power_in"))
      (node (ref "ENC") (pin "22") (pinfunction "VSSOSC_22") (pintype "power_in"))
      (node (ref "ER10") (pin "2") (pinfunction "2_2") (pintype "passive"))
      (node (ref "GPIO") (pin "3") (pinfunction "S_3") (pintype "passive"))
      (node (ref "IC1") (pin "10") (pinfunction "VSS_10") (pintype "power_in"))
      (node (ref "IC1") (pin "16") (pinfunction "A1_16") (pintype "input"))
      (node (ref "IC1") (pin "17") (pinfunction "A2_17") (pintype "input"))
      (node (ref "INDL") (pin "C") (pinfunction "C_C") (pintype "passive"))
      (node (ref "IR1") (pin "5") (pinfunction "2_5") (pintype "passive"))
      (node (ref "IR1") (pin "6") (pinfunction "2_6") (pintype "passive"))
      (node (ref "IR1") (pin "7") (pinfunction "2_7") (pintype "passive"))
      (node (ref "IR1") (pin "8") (pinfunction "2_8") (pintype "passive"))
      (node (ref "IR2") (pin "5") (pinfunction "2_5") (pintype "passive"))
      (node (ref "IR2") (pin "6") (pinfunction "2_6") (pintype "passive"))
      (node (ref "IR2") (pin "7") (pinfunction "2_7") (pintype "passive"))
      (node (ref "IR2") (pin "8") (pinfunction "2_8") (pintype "passive"))
      (node (ref "IR3") (pin "1") (pinfunction "1_1") (pintype "passive"))
      (node (ref "IR3") (pin "2") (pinfunction "1_2") (pintype "passive"))
      (node (ref "IR3") (pin "3") (pinfunction "1_3") (pintype "passive"))
      (node (ref "IR3") (pin "4") (pinfunction "1_4") (pintype "passive"))
      (node (ref "IR4") (pin "1") (pinfunction "1_1") (pintype "passive"))
      (node (ref "IR4") (pin "2") (pinfunction "1_2") (pintype "passive"))
      (node (ref "IR4") (pin "3") (pinfunction "1_3") (pintype "passive"))
      (node (ref "IR4") (pin "4") (pinfunction "1_4") (pintype "passive"))
      (node (ref "MC") (pin "21") (pinfunction "GND_21") (pintype "bidirectional"))
      (node (ref "MC") (pin "3") (pinfunction "GND_3") (pintype "bidirectional"))
      (node (ref "MC") (pin "5") (pinfunction "AGND_5") (pintype "bidirectional"))
      (node (ref "NI") (pin "2") (pinfunction "SK_2") (pintype "passive"))
      (node (ref "OK3") (pin "2") (pinfunction "C_2") (pintype "passive"))
      (node (ref "OK3") (pin "4") (pinfunction "C_4") (pintype "passive"))
      (node (ref "OK3") (pin "6") (pinfunction "C_6") (pintype "passive"))
      (node (ref "OK3") (pin "8") (pinfunction "C_8") (pintype "passive"))
      (node (ref "OK4") (pin "2") (pinfunction "C_2") (pintype "passive"))
      (node (ref "OK4") (pin "4") (pinfunction "C_4") (pintype "passive"))
      (node (ref "OK4") (pin "6") (pinfunction "C_6") (pintype "passive"))
      (node (ref "OK4") (pin "8") (pinfunction "C_8") (pintype "passive"))
      (node (ref "OL1") (pin "C") (pinfunction "C_C") (pintype "passive"))
      (node (ref "OL2") (pin "C") (pinfunction "C_C") (pintype "passive"))
      (node (ref "OL3") (pin "C") (pinfunction "C_C") (pintype "passive"))
      (node (ref "OL4") (pin "C") (pinfunction "C_C") (pintype "passive"))
      (node (ref "OL5") (pin "C") (pinfunction "C_C") (pintype "passive"))
      (node (ref "OL6") (pin "C") (pinfunction "C_C") (pintype "passive"))
      (node (ref "OL7") (pin "C") (pinfunction "C_C") (pintype "passive"))
      (node (ref "OL8") (pin "C") (pinfunction "C_C") (pintype "passive"))
      (node (ref "PC1") (pin "-") (pinfunction "-_-") (pintype "passive"))
      (node (ref "PC2") (pin "-") (pinfunction "-_-") (pintype "passive"))
      (node (ref "PD2") (pin "A") (pinfunction "A_A") (pintype "passive"))
      (node (ref "PIC33") (pin "3") (pinfunction "GND_3") (pintype "power_in"))
      (node (ref "PIC33") (pin "5") (pinfunction "~{ON}/OFF_5") (pintype "input"))
      (node (ref "PJ1") (pin "GND") (pinfunction "GNDBREAK_GND") (pintype "bidirectional"))
      (node (ref "PL") (pin "C") (pinfunction "C_C") (pintype "passive"))
      (node (ref "PP") (pin "2") (pinfunction "S_2") (pintype "passive"))
      (node (ref "Q1") (pin "2") (pinfunction "2_2") (pintype "passive"))
      (node (ref "SC1") (pin "2") (pinfunction "2_2") (pintype "passive"))
      (node (ref "SHT") (pin "ADDR") (pinfunction "ADDR_ADDR") (pintype "bidirectional"))
      (node (ref "SHT") (pin "GND") (pinfunction "GND_GND") (pintype "bidirectional"))
      (node (ref "SHT") (pin "GND_PAD") (pinfunction "GND_PAD_GND_PAD") (pintype "bidirectional"))
      (node (ref "SHT") (pin "R") (pinfunction "R_R") (pintype "bidirectional"))
      (node (ref "SR") (pin "2") (pinfunction "S_2") (pintype "passive"))
      (node (ref "TR") (pin "1") (pinfunction "1_1") (pintype "passive"))
      (node (ref "U$2") (pin "G-") (pinfunction "G-_G-") (pintype "bidirectional"))
      (node (ref "U$2") (pin "GND") (pinfunction "GND_GND") (pintype "bidirectional"))
      (node (ref "U$2") (pin "SHIELD1") (pinfunction "SHIELD0_SHIELD1") (pintype "bidirectional"))
      (node (ref "U$2") (pin "SHIELD2") (pinfunction "SHIELD1_SHIELD2") (pintype "bidirectional"))
      (node (ref "U$2") (pin "Y-") (pinfunction "Y-_Y-") (pintype "bidirectional"))
      (node (ref "WIFI") (pin "GND") (pinfunction "GND_GND") (pintype "bidirectional"))
      (node (ref "XV") (pin "1") (pinfunction "SK_1") (pintype "passive"))
    )
    (net (code "28") (name "GNDO") (class "Default")
      (node (ref "EC6") (pin "-") (pinfunction "-_-") (pintype "passive"))
      (node (ref "OD2") (pin "A") (pinfunction "A_A") (pintype "passive"))
      (node (ref "OR2") (pin "5") (pinfunction "2_5") (pintype "passive"))
      (node (ref "OR2") (pin "6") (pinfunction "2_6") (pintype "passive"))
      (node (ref "OR2") (pin "7") (pinfunction "2_7") (pintype "passive"))
      (node (ref "OR2") (pin "8") (pinfunction "2_8") (pintype "passive"))
      (node (ref "OR6") (pin "5") (pinfunction "2_5") (pintype "passive"))
      (node (ref "OR6") (pin "6") (pinfunction "2_6") (pintype "passive"))
      (node (ref "OR6") (pin "7") (pinfunction "2_7") (pintype "passive"))
      (node (ref "OR6") (pin "8") (pinfunction "2_8") (pintype "passive"))
      (node (ref "U1") (pin "9") (pinfunction "GND_9") (pintype "passive"))
      (node (ref "XO") (pin "2") (pinfunction "SK_2") (pintype "passive"))
    )
    (net (code "29") (name "GPA0") (class "Default")
      (node (ref "IC1") (pin "21") (pinfunction "GPA0_21") (pintype "bidirectional"))
      (node (ref "IL1") (pin "A") (pinfunction "A_A") (pintype "passive"))
      (node (ref "IR1") (pin "4") (pinfunction "1_4") (pintype "passive"))
      (node (ref "OK1") (pin "15") (pinfunction "EMIT_15") (pintype "passive"))
    )
    (net (code "30") (name "GPA1") (class "Default")
      (node (ref "IC1") (pin "22") (pinfunction "GPA1_22") (pintype "bidirectional"))
      (node (ref "IL2") (pin "A") (pinfunction "A_A") (pintype "passive"))
      (node (ref "IR1") (pin "3") (pinfunction "1_3") (pintype "passive"))
      (node (ref "OK1") (pin "13") (pinfunction "EMIT_13") (pintype "passive"))
    )
    (net (code "31") (name "GPA2") (class "Default")
      (node (ref "IC1") (pin "23") (pinfunction "GPA2_23") (pintype "bidirectional"))
      (node (ref "IL3") (pin "A") (pinfunction "A_A") (pintype "passive"))
      (node (ref "IR1") (pin "2") (pinfunction "1_2") (pintype "passive"))
      (node (ref "OK1") (pin "11") (pinfunction "EMIT_11") (pintype "passive"))
    )
    (net (code "32") (name "GPA3") (class "Default")
      (node (ref "IC1") (pin "24") (pinfunction "GPA3_24") (pintype "bidirectional"))
      (node (ref "IL4") (pin "A") (pinfunction "A_A") (pintype "passive"))
      (node (ref "IR1") (pin "1") (pinfunction "1_1") (pintype "passive"))
      (node (ref "OK1") (pin "9") (pinfunction "EMIT_9") (pintype "passive"))
    )
    (net (code "33") (name "GPA4") (class "Default")
      (node (ref "IC1") (pin "25") (pinfunction "GPA4_25") (pintype "bidirectional"))
      (node (ref "IL5") (pin "A") (pinfunction "A_A") (pintype "passive"))
      (node (ref "IR2") (pin "4") (pinfunction "1_4") (pintype "passive"))
      (node (ref "OK2") (pin "15") (pinfunction "EMIT_15") (pintype "passive"))
    )
    (net (code "34") (name "GPA5") (class "Default")
      (node (ref "IC1") (pin "26") (pinfunction "GPA5_26") (pintype "bidirectional"))
      (node (ref "IL6") (pin "A") (pinfunction "A_A") (pintype "passive"))
      (node (ref "IR2") (pin "3") (pinfunction "1_3") (pintype "passive"))
      (node (ref "OK2") (pin "13") (pinfunction "EMIT_13") (pintype "passive"))
    )
    (net (code "35") (name "GPA6") (class "Default")
      (node (ref "IC1") (pin "27") (pinfunction "GPA6_27") (pintype "bidirectional"))
      (node (ref "IL7") (pin "A") (pinfunction "A_A") (pintype "passive"))
      (node (ref "IR2") (pin "2") (pinfunction "1_2") (pintype "passive"))
      (node (ref "OK2") (pin "11") (pinfunction "EMIT_11") (pintype "passive"))
    )
    (net (code "36") (name "GPA7") (class "Default")
      (node (ref "IC1") (pin "28") (pinfunction "GPA7_28") (pintype "bidirectional"))
      (node (ref "IL8") (pin "A") (pinfunction "A_A") (pintype "passive"))
      (node (ref "IR2") (pin "1") (pinfunction "1_1") (pintype "passive"))
      (node (ref "OK2") (pin "9") (pinfunction "EMIT_9") (pintype "passive"))
    )
    (net (code "37") (name "GPB0") (class "Default")
      (node (ref "IC1") (pin "1") (pinfunction "GPB0_1") (pintype "bidirectional"))
      (node (ref "OR4") (pin "8") (pinfunction "2_8") (pintype "passive"))
      (node (ref "OR8") (pin "8") (pinfunction "2_8") (pintype "passive"))
    )
    (net (code "38") (name "GPB1") (class "Default")
      (node (ref "IC1") (pin "2") (pinfunction "GPB1_2") (pintype "bidirectional"))
      (node (ref "OR4") (pin "7") (pinfunction "2_7") (pintype "passive"))
      (node (ref "OR8") (pin "7") (pinfunction "2_7") (pintype "passive"))
    )
    (net (code "39") (name "GPB2") (class "Default")
      (node (ref "IC1") (pin "3") (pinfunction "GPB2_3") (pintype "bidirectional"))
      (node (ref "OR4") (pin "6") (pinfunction "2_6") (pintype "passive"))
      (node (ref "OR8") (pin "6") (pinfunction "2_6") (pintype "passive"))
    )
    (net (code "40") (name "GPB3") (class "Default")
      (node (ref "IC1") (pin "4") (pinfunction "GPB3_4") (pintype "bidirectional"))
      (node (ref "OR4") (pin "5") (pinfunction "2_5") (pintype "passive"))
      (node (ref "OR8") (pin "5") (pinfunction "2_5") (pintype "passive"))
    )
    (net (code "41") (name "GPB4") (class "Default")
      (node (ref "IC1") (pin "5") (pinfunction "GPB4_5") (pintype "bidirectional"))
      (node (ref "OR1") (pin "8") (pinfunction "2_8") (pintype "passive"))
      (node (ref "OR7") (pin "8") (pinfunction "2_8") (pintype "passive"))
    )
    (net (code "42") (name "GPB5") (class "Default")
      (node (ref "IC1") (pin "6") (pinfunction "GPB5_6") (pintype "bidirectional"))
      (node (ref "OR1") (pin "7") (pinfunction "2_7") (pintype "passive"))
      (node (ref "OR7") (pin "7") (pinfunction "2_7") (pintype "passive"))
    )
    (net (code "43") (name "GPB6") (class "Default")
      (node (ref "IC1") (pin "7") (pinfunction "GPB6_7") (pintype "bidirectional"))
      (node (ref "OR1") (pin "6") (pinfunction "2_6") (pintype "passive"))
      (node (ref "OR7") (pin "6") (pinfunction "2_6") (pintype "passive"))
    )
    (net (code "44") (name "GPB7") (class "Default")
      (node (ref "IC1") (pin "8") (pinfunction "GPB7_8") (pintype "bidirectional"))
      (node (ref "OR1") (pin "5") (pinfunction "2_5") (pintype "passive"))
      (node (ref "OR7") (pin "5") (pinfunction "2_5") (pintype "passive"))
    )
    (net (code "45") (name "IO5") (class "Default")
      (node (ref "OK4") (pin "15") (pinfunction "EMIT_15") (pintype "passive"))
      (node (ref "OR6") (pin "1") (pinfunction "1_1") (pintype "passive"))
      (node (ref "U1") (pin "4") (pinfunction "4B_4") (pintype "input"))
    )
    (net (code "46") (name "IO6") (class "Default")
      (node (ref "OK4") (pin "13") (pinfunction "EMIT_13") (pintype "passive"))
      (node (ref "OR6") (pin "2") (pinfunction "1_2") (pintype "passive"))
      (node (ref "U1") (pin "3") (pinfunction "3B_3") (pintype "input"))
    )
    (net (code "47") (name "IO7") (class "Default")
      (node (ref "OK4") (pin "11") (pinfunction "EMIT_11") (pintype "passive"))
      (node (ref "OR6") (pin "3") (pinfunction "1_3") (pintype "passive"))
      (node (ref "U1") (pin "2") (pinfunction "2B_2") (pintype "input"))
    )
    (net (code "48") (name "IO8") (class "Default")
      (node (ref "OK4") (pin "9") (pinfunction "EMIT_9") (pintype "passive"))
      (node (ref "OR6") (pin "4") (pinfunction "1_4") (pintype "passive"))
      (node (ref "U1") (pin "1") (pinfunction "1B_1") (pintype "input"))
    )
    (net (code "49") (name "LEDA") (class "Default")
      (node (ref "ER3") (pin "1") (pinfunction "1_1") (pintype "passive"))
      (node (ref "U$2") (pin "Y+") (pinfunction "Y+_Y+") (pintype "bidirectional"))
    )
    (net (code "50") (name "LEDB") (class "Default")
      (node (ref "ER4") (pin "1") (pinfunction "1_1") (pintype "passive"))
      (node (ref "U$2") (pin "G+") (pinfunction "G+_G+") (pintype "bidirectional"))
    )
    (net (code "51") (name "Net-(ENC-LEDA)") (class "Default")
      (node (ref "ENC") (pin "27") (pinfunction "LEDA_27") (pintype "output"))
      (node (ref "ER3") (pin "2") (pinfunction "2_2") (pintype "passive"))
    )
    (net (code "52") (name "Net-(ENC-LEDB)") (class "Default")
      (node (ref "ENC") (pin "26") (pinfunction "LEDB_26") (pintype "output"))
      (node (ref "ER4") (pin "2") (pinfunction "2_2") (pintype "passive"))
    )
    (net (code "53") (name "Net-(ENC-OSC1)") (class "Default")
      (node (ref "EC1") (pin "1") (pinfunction "1_1") (pintype "passive"))
      (node (ref "ENC") (pin "23") (pinfunction "OSC1_23") (pintype "input"))
      (node (ref "Q2") (pin "2") (pinfunction "2_2") (pintype "passive"))
    )
    (net (code "54") (name "Net-(ENC-OSC2)") (class "Default")
      (node (ref "EC2") (pin "1") (pinfunction "1_1") (pintype "passive"))
      (node (ref "ENC") (pin "24") (pinfunction "OSC2_24") (pintype "output"))
      (node (ref "Q2") (pin "1") (pinfunction "1_1") (pintype "passive"))
    )
    (net (code "55") (name "Net-(ENC-RBIAS)") (class "Default")
      (node (ref "ENC") (pin "14") (pinfunction "RBIAS_14") (pintype "passive"))
      (node (ref "ER10") (pin "1") (pinfunction "1_1") (pintype "passive"))
    )
    (net (code "56") (name "Net-(ENC-RESET)") (class "Default")
      (node (ref "ENC") (pin "10") (pinfunction "RESET_10") (pintype "input"))
      (node (ref "ER1") (pin "1") (pinfunction "1_1") (pintype "passive"))
    )
    (net (code "57") (name "Net-(ENC-TPIN+)") (class "Default")
      (node (ref "ENC") (pin "13") (pinfunction "TPIN+_13") (pintype "input"))
      (node (ref "ERN1") (pin "6") (pinfunction "2_6") (pintype "passive"))
      (node (ref "U$2") (pin "RD+") (pinfunction "RD+_RD+") (pintype "bidirectional"))
    )
    (net (code "58") (name "Net-(ENC-TPIN-)") (class "Default")
      (node (ref "ENC") (pin "12") (pinfunction "TPIN-_12") (pintype "input"))
      (node (ref "ERN1") (pin "5") (pinfunction "2_5") (pintype "passive"))
      (node (ref "U$2") (pin "RD-") (pinfunction "RD-_RD-") (pintype "bidirectional"))
    )
    (net (code "59") (name "Net-(ENC-TPOUT+)") (class "Default")
      (node (ref "ENC") (pin "17") (pinfunction "TPOUT+_17") (pintype "output"))
      (node (ref "ERN1") (pin "1") (pinfunction "1_1") (pintype "passive"))
      (node (ref "U$2") (pin "TD+") (pinfunction "TD+_TD+") (pintype "bidirectional"))
    )
    (net (code "60") (name "Net-(ENC-TPOUT-)") (class "Default")
      (node (ref "ENC") (pin "16") (pinfunction "TPOUT-_16") (pintype "output"))
      (node (ref "ERN1") (pin "2") (pinfunction "1_2") (pintype "passive"))
      (node (ref "U$2") (pin "TD-") (pinfunction "TD-_TD-") (pintype "bidirectional"))
    )
    (net (code "61") (name "Net-(ENC-VCAP)") (class "Default")
      (node (ref "EC3") (pin "+") (pinfunction "+_+") (pintype "passive"))
      (node (ref "ENC") (pin "1") (pinfunction "VCAP_1") (pintype "power_in"))
    )
    (net (code "62") (name "Net-(ERN1A-2)") (class "Default")
      (node (ref "EC4") (pin "1") (pinfunction "1_1") (pintype "passive"))
      (node (ref "EL1") (pin "2") (pinfunction "2_2") (pintype "passive"))
      (node (ref "ERN1") (pin "7") (pinfunction "2_7") (pintype "passive"))
      (node (ref "ERN1") (pin "8") (pinfunction "2_8") (pintype "passive"))
      (node (ref "U$2") (pin "P4") (pinfunction "P4_P4") (pintype "bidirectional"))
    )
    (net (code "63") (name "Net-(ERN1C-1)") (class "Default")
      (node (ref "EC5") (pin "1") (pinfunction "1_1") (pintype "passive"))
      (node (ref "ERN1") (pin "3") (pinfunction "1_3") (pintype "passive"))
      (node (ref "ERN1") (pin "4") (pinfunction "1_4") (pintype "passive"))
      (node (ref "U$2") (pin "P5") (pinfunction "P5_P5") (pintype "bidirectional"))
    )
    (net (code "64") (name "Net-(IC1-A0)") (class "Default")
      (node (ref "IC1") (pin "15") (pinfunction "A0_15") (pintype "input"))
      (node (ref "MR3") (pin "1") (pinfunction "1_1") (pintype "passive"))
    )
    (net (code "65") (name "Net-(IIR1A-2)") (class "Default")
      (node (ref "IIR1") (pin "8") (pinfunction "2_8") (pintype "passive"))
      (node (ref "OK1") (pin "1") (pinfunction "A_1") (pintype "passive"))
    )
    (net (code "66") (name "Net-(IIR1B-1)") (class "Default")
      (node (ref "IIR1") (pin "2") (pinfunction "1_2") (pintype "passive"))
      (node (ref "XI1") (pin "3") (pinfunction "SK_3") (pintype "passive"))
    )
    (net (code "67") (name "Net-(IIR1B-2)") (class "Default")
      (node (ref "IIR1") (pin "7") (pinfunction "2_7") (pintype "passive"))
      (node (ref "OK1") (pin "3") (pinfunction "A_3") (pintype "passive"))
    )
    (net (code "68") (name "Net-(IIR1C-1)") (class "Default")
      (node (ref "IIR1") (pin "3") (pinfunction "1_3") (pintype "passive"))
      (node (ref "XI1") (pin "4") (pinfunction "SK_4") (pintype "passive"))
    )
    (net (code "69") (name "Net-(IIR1C-2)") (class "Default")
      (node (ref "IIR1") (pin "6") (pinfunction "2_6") (pintype "passive"))
      (node (ref "OK1") (pin "5") (pinfunction "A_5") (pintype "passive"))
    )
    (net (code "70") (name "Net-(IIR1D-1)") (class "Default")
      (node (ref "IIR1") (pin "4") (pinfunction "1_4") (pintype "passive"))
      (node (ref "XI1") (pin "5") (pinfunction "SK_5") (pintype "passive"))
    )
    (net (code "71") (name "Net-(IIR1D-2)") (class "Default")
      (node (ref "IIR1") (pin "5") (pinfunction "2_5") (pintype "passive"))
      (node (ref "OK1") (pin "7") (pinfunction "A_7") (pintype "passive"))
    )
    (net (code "72") (name "Net-(IIR2A-2)") (class "Default")
      (node (ref "IIR2") (pin "8") (pinfunction "2_8") (pintype "passive"))
      (node (ref "OK2") (pin "1") (pinfunction "A_1") (pintype "passive"))
    )
    (net (code "73") (name "Net-(IIR2B-1)") (class "Default")
      (node (ref "IIR2") (pin "2") (pinfunction "1_2") (pintype "passive"))
      (node (ref "XI2") (pin "3") (pinfunction "SK_3") (pintype "passive"))
    )
    (net (code "74") (name "Net-(IIR2B-2)") (class "Default")
      (node (ref "IIR2") (pin "7") (pinfunction "2_7") (pintype "passive"))
      (node (ref "OK2") (pin "3") (pinfunction "A_3") (pintype "passive"))
    )
    (net (code "75") (name "Net-(IIR2C-1)") (class "Default")
      (node (ref "IIR2") (pin "3") (pinfunction "1_3") (pintype "passive"))
      (node (ref "XI2") (pin "4") (pinfunction "SK_4") (pintype "passive"))
    )
    (net (code "76") (name "Net-(IIR2C-2)") (class "Default")
      (node (ref "IIR2") (pin "6") (pinfunction "2_6") (pintype "passive"))
      (node (ref "OK2") (pin "5") (pinfunction "A_5") (pintype "passive"))
    )
    (net (code "77") (name "Net-(IIR2D-1)") (class "Default")
      (node (ref "IIR2") (pin "4") (pinfunction "1_4") (pintype "passive"))
      (node (ref "XI2") (pin "5") (pinfunction "SK_5") (pintype "passive"))
    )
    (net (code "78") (name "Net-(IIR2D-2)") (class "Default")
      (node (ref "IIR2") (pin "5") (pinfunction "2_5") (pintype "passive"))
      (node (ref "OK2") (pin "7") (pinfunction "A_7") (pintype "passive"))
    )
    (net (code "79") (name "Net-(INDL-PadA)") (class "Default")
      (node (ref "INDL") (pin "A") (pinfunction "A_A") (pintype "passive"))
      (node (ref "R6") (pin "2") (pinfunction "2_2") (pintype "passive"))
    )
    (net (code "80") (name "Net-(IR3A-2)") (class "Default")
      (node (ref "IL1") (pin "C") (pinfunction "C_C") (pintype "passive"))
      (node (ref "IR3") (pin "8") (pinfunction "2_8") (pintype "passive"))
    )
    (net (code "81") (name "Net-(IR3B-2)") (class "Default")
      (node (ref "IL2") (pin "C") (pinfunction "C_C") (pintype "passive"))
      (node (ref "IR3") (pin "7") (pinfunction "2_7") (pintype "passive"))
    )
    (net (code "82") (name "Net-(IR3C-2)") (class "Default")
      (node (ref "IL3") (pin "C") (pinfunction "C_C") (pintype "passive"))
      (node (ref "IR3") (pin "6") (pinfunction "2_6") (pintype "passive"))
    )
    (net (code "83") (name "Net-(IR3D-2)") (class "Default")
      (node (ref "IL4") (pin "C") (pinfunction "C_C") (pintype "passive"))
      (node (ref "IR3") (pin "5") (pinfunction "2_5") (pintype "passive"))
    )
    (net (code "84") (name "Net-(IR4A-2)") (class "Default")
      (node (ref "IL5") (pin "C") (pinfunction "C_C") (pintype "passive"))
      (node (ref "IR4") (pin "8") (pinfunction "2_8") (pintype "passive"))
    )
    (net (code "85") (name "Net-(IR4B-2)") (class "Default")
      (node (ref "IL6") (pin "C") (pinfunction "C_C") (pintype "passive"))
      (node (ref "IR4") (pin "7") (pinfunction "2_7") (pintype "passive"))
    )
    (net (code "86") (name "Net-(IR4C-2)") (class "Default")
      (node (ref "IL7") (pin "C") (pinfunction "C_C") (pintype "passive"))
      (node (ref "IR4") (pin "6") (pinfunction "2_6") (pintype "passive"))
    )
    (net (code "87") (name "Net-(IR4D-2)") (class "Default")
      (node (ref "IL8") (pin "C") (pinfunction "C_C") (pintype "passive"))
      (node (ref "IR4") (pin "5") (pinfunction "2_5") (pintype "passive"))
    )
    (net (code "88") (name "Net-(MC-PB6(XTAL1{slash}TOSC1))") (class "Default")
      (node (ref "MC") (pin "7") (pinfunction "PB6(XTAL1/TOSC1)_7") (pintype "bidirectional"))
      (node (ref "Q1") (pin "1") (pinfunction "1_1") (pintype "passive"))
    )
    (net (code "89") (name "Net-(MC-PB7(XTAL2{slash}TOSC2))") (class "Default")
      (node (ref "MC") (pin "8") (pinfunction "PB7(XTAL2/TOSC2)_8") (pintype "bidirectional"))
      (node (ref "Q1") (pin "3") (pinfunction "3_3") (pintype "passive"))
    )
    (net (code "90") (name "Net-(OD1-PadC)") (class "Default")
      (node (ref "OD1") (pin "C") (pinfunction "C_C") (pintype "passive"))
      (node (ref "OMF") (pin "2") (pinfunction "2_2") (pintype "bidirectional"))
    )
    (net (code "91") (name "Net-(OK3A-A)") (class "Default")
      (node (ref "OK3") (pin "1") (pinfunction "A_1") (pintype "passive"))
      (node (ref "OR1") (pin "4") (pinfunction "1_4") (pintype "passive"))
    )
    (net (code "92") (name "Net-(OK3A-COL)") (class "Default")
      (node (ref "OK3") (pin "16") (pinfunction "COL_16") (pintype "passive"))
      (node (ref "OR3") (pin "1") (pinfunction "1_1") (pintype "passive"))
    )
    (net (code "93") (name "Net-(OK3B-A)") (class "Default")
      (node (ref "OK3") (pin "3") (pinfunction "A_3") (pintype "passive"))
      (node (ref "OR1") (pin "3") (pinfunction "1_3") (pintype "passive"))
    )
    (net (code "94") (name "Net-(OK3B-COL)") (class "Default")
      (node (ref "OK3") (pin "14") (pinfunction "COL_14") (pintype "passive"))
      (node (ref "OR3") (pin "2") (pinfunction "1_2") (pintype "passive"))
    )
    (net (code "95") (name "Net-(OK3C-A)") (class "Default")
      (node (ref "OK3") (pin "5") (pinfunction "A_5") (pintype "passive"))
      (node (ref "OR1") (pin "2") (pinfunction "1_2") (pintype "passive"))
    )
    (net (code "96") (name "Net-(OK3C-COL)") (class "Default")
      (node (ref "OK3") (pin "12") (pinfunction "COL_12") (pintype "passive"))
      (node (ref "OR3") (pin "3") (pinfunction "1_3") (pintype "passive"))
    )
    (net (code "97") (name "Net-(OK3D-A)") (class "Default")
      (node (ref "OK3") (pin "7") (pinfunction "A_7") (pintype "passive"))
      (node (ref "OR1") (pin "1") (pinfunction "1_1") (pintype "passive"))
    )
    (net (code "98") (name "Net-(OK3D-COL)") (class "Default")
      (node (ref "OK3") (pin "10") (pinfunction "COL_10") (pintype "passive"))
      (node (ref "OR3") (pin "4") (pinfunction "1_4") (pintype "passive"))
    )
    (net (code "99") (name "Net-(OK4A-A)") (class "Default")
      (node (ref "OK4") (pin "1") (pinfunction "A_1") (pintype "passive"))
      (node (ref "OR4") (pin "4") (pinfunction "1_4") (pintype "passive"))
    )
    (net (code "100") (name "Net-(OK4A-COL)") (class "Default")
      (node (ref "OK4") (pin "16") (pinfunction "COL_16") (pintype "passive"))
      (node (ref "OR5") (pin "1") (pinfunction "1_1") (pintype "passive"))
    )
    (net (code "101") (name "Net-(OK4B-A)") (class "Default")
      (node (ref "OK4") (pin "3") (pinfunction "A_3") (pintype "passive"))
      (node (ref "OR4") (pin "3") (pinfunction "1_3") (pintype "passive"))
    )
    (net (code "102") (name "Net-(OK4B-COL)") (class "Default")
      (node (ref "OK4") (pin "14") (pinfunction "COL_14") (pintype "passive"))
      (node (ref "OR5") (pin "2") (pinfunction "1_2") (pintype "passive"))
    )
    (net (code "103") (name "Net-(OK4C-A)") (class "Default")
      (node (ref "OK4") (pin "5") (pinfunction "A_5") (pintype "passive"))
      (node (ref "OR4") (pin "2") (pinfunction "1_2") (pintype "passive"))
    )
    (net (code "104") (name "Net-(OK4C-COL)") (class "Default")
      (node (ref "OK4") (pin "12") (pinfunction "COL_12") (pintype "passive"))
      (node (ref "OR5") (pin "3") (pinfunction "1_3") (pintype "passive"))
    )
    (net (code "105") (name "Net-(OK4D-A)") (class "Default")
      (node (ref "OK4") (pin "7") (pinfunction "A_7") (pintype "passive"))
      (node (ref "OR4") (pin "1") (pinfunction "1_1") (pintype "passive"))
    )
    (net (code "106") (name "Net-(OK4D-COL)") (class "Default")
      (node (ref "OK4") (pin "10") (pinfunction "COL_10") (pintype "passive"))
      (node (ref "OR5") (pin "4") (pinfunction "1_4") (pintype "passive"))
    )
    (net (code "107") (name "Net-(OL4-PadA)") (class "Default")
      (node (ref "OL4") (pin "A") (pinfunction "A_A") (pintype "passive"))
      (node (ref "OR7") (pin "1") (pinfunction "1_1") (pintype "passive"))
    )
    (net (code "108") (name "Net-(OL8-PadA)") (class "Default")
      (node (ref "OL8") (pin "A") (pinfunction "A_A") (pintype "passive"))
      (node (ref "OR8") (pin "1") (pinfunction "1_1") (pintype "passive"))
    )
    (net (code "109") (name "Net-(OR7B-1)") (class "Default")
      (node (ref "OL3") (pin "A") (pinfunction "A_A") (pintype "passive"))
      (node (ref "OR7") (pin "2") (pinfunction "1_2") (pintype "passive"))
    )
    (net (code "110") (name "Net-(OR7C-1)") (class "Default")
      (node (ref "OL2") (pin "A") (pinfunction "A_A") (pintype "passive"))
      (node (ref "OR7") (pin "3") (pinfunction "1_3") (pintype "passive"))
    )
    (net (code "111") (name "Net-(OR7D-1)") (class "Default")
      (node (ref "OL1") (pin "A") (pinfunction "A_A") (pintype "passive"))
      (node (ref "OR7") (pin "4") (pinfunction "1_4") (pintype "passive"))
    )
    (net (code "112") (name "Net-(OR8B-1)") (class "Default")
      (node (ref "OL7") (pin "A") (pinfunction "A_A") (pintype "passive"))
      (node (ref "OR8") (pin "2") (pinfunction "1_2") (pintype "passive"))
    )
    (net (code "113") (name "Net-(OR8C-1)") (class "Default")
      (node (ref "OL6") (pin "A") (pinfunction "A_A") (pintype "passive"))
      (node (ref "OR8") (pin "3") (pinfunction "1_3") (pintype "passive"))
    )
    (net (code "114") (name "Net-(OR8D-1)") (class "Default")
      (node (ref "OL5") (pin "A") (pinfunction "A_A") (pintype "passive"))
      (node (ref "OR8") (pin "4") (pinfunction "1_4") (pintype "passive"))
    )
    (net (code "115") (name "Net-(PD1-PadC)") (class "Default")
      (node (ref "PD1") (pin "C") (pinfunction "C_C") (pintype "passive"))
      (node (ref "PF1") (pin "1") (pinfunction "1_1") (pintype "passive"))
    )
    (net (code "116") (name "Net-(PIC33-OUT)") (class "Default")
      (node (ref "PCO") (pin "P$2") (pinfunction "P$2_P$2") (pintype "passive"))
      (node (ref "PD2") (pin "C") (pinfunction "C_C") (pintype "passive"))
      (node (ref "PIC33") (pin "2") (pinfunction "OUT_2") (pintype "output"))
    )
    (net (code "117") (name "Net-(PL-PadA)") (class "Default")
      (node (ref "PL") (pin "A") (pinfunction "A_A") (pintype "passive"))
      (node (ref "PR1") (pin "1") (pinfunction "1_1") (pintype "passive"))
    )
    (net (code "118") (name "Net-(U1-1C)") (class "Default")
      (node (ref "D1") (pin "2") (pinfunction "2_2") (pintype "bidirectional"))
      (node (ref "OF8") (pin "2") (pinfunction "2_2") (pintype "bidirectional"))
      (node (ref "U1") (pin "18") (pinfunction "1C_18") (pintype "output"))
    )
    (net (code "119") (name "Net-(U1-2C)") (class "Default")
      (node (ref "D1") (pin "1") (pinfunction "1_1") (pintype "bidirectional"))
      (node (ref "OF7") (pin "2") (pinfunction "2_2") (pintype "bidirectional"))
      (node (ref "U1") (pin "17") (pinfunction "2C_17") (pintype "output"))
    )
    (net (code "120") (name "Net-(U1-3C)") (class "Default")
      (node (ref "D2") (pin "2") (pinfunction "2_2") (pintype "bidirectional"))
      (node (ref "OF6") (pin "2") (pinfunction "2_2") (pintype "bidirectional"))
      (node (ref "U1") (pin "16") (pinfunction "3C_16") (pintype "output"))
    )
    (net (code "121") (name "Net-(U1-4C)") (class "Default")
      (node (ref "D2") (pin "1") (pinfunction "1_1") (pintype "bidirectional"))
      (node (ref "OF5") (pin "2") (pinfunction "2_2") (pintype "bidirectional"))
      (node (ref "U1") (pin "15") (pinfunction "4C_15") (pintype "output"))
    )
    (net (code "122") (name "Net-(U1-5C)") (class "Default")
      (node (ref "D3") (pin "2") (pinfunction "2_2") (pintype "bidirectional"))
      (node (ref "OF4") (pin "2") (pinfunction "2_2") (pintype "bidirectional"))
      (node (ref "U1") (pin "14") (pinfunction "5C_14") (pintype "output"))
    )
    (net (code "123") (name "Net-(U1-6C)") (class "Default")
      (node (ref "D3") (pin "1") (pinfunction "1_1") (pintype "bidirectional"))
      (node (ref "OF3") (pin "2") (pinfunction "2_2") (pintype "bidirectional"))
      (node (ref "U1") (pin "13") (pinfunction "6C_13") (pintype "output"))
    )
    (net (code "124") (name "Net-(U1-7C)") (class "Default")
      (node (ref "D4") (pin "2") (pinfunction "2_2") (pintype "bidirectional"))
      (node (ref "OF2") (pin "2") (pinfunction "2_2") (pintype "bidirectional"))
      (node (ref "U1") (pin "12") (pinfunction "7C_12") (pintype "output"))
    )
    (net (code "125") (name "Net-(U1-8C)") (class "Default")
      (node (ref "D4") (pin "1") (pinfunction "1_1") (pintype "bidirectional"))
      (node (ref "OF1") (pin "2") (pinfunction "2_2") (pintype "bidirectional"))
      (node (ref "U1") (pin "11") (pinfunction "8C_11") (pintype "output"))
    )
    (net (code "126") (name "Net-(XI1B-SK)") (class "Default")
      (node (ref "IIR1") (pin "1") (pinfunction "1_1") (pintype "passive"))
      (node (ref "XI1") (pin "2") (pinfunction "SK_2") (pintype "passive"))
    )
    (net (code "127") (name "Net-(XI2B-SK)") (class "Default")
      (node (ref "IIR2") (pin "1") (pinfunction "1_1") (pintype "passive"))
      (node (ref "XI2") (pin "2") (pinfunction "SK_2") (pintype "passive"))
    )
    (net (code "128") (name "Net-(XOA-SK)") (class "Default")
      (node (ref "OD1") (pin "A") (pinfunction "A_A") (pintype "passive"))
      (node (ref "XO") (pin "1") (pinfunction "SK_1") (pintype "passive"))
    )
    (net (code "129") (name "Net-(XOB-SK)") (class "Default")
      (node (ref "OF8") (pin "1") (pinfunction "1_1") (pintype "bidirectional"))
      (node (ref "XO") (pin "10") (pinfunction "SK_10") (pintype "passive"))
    )
    (net (code "130") (name "Net-(XOD-SK)") (class "Default")
      (node (ref "OF1") (pin "1") (pinfunction "1_1") (pintype "bidirectional"))
      (node (ref "XO") (pin "3") (pinfunction "SK_3") (pintype "passive"))
    )
    (net (code "131") (name "Net-(XOE-SK)") (class "Default")
      (node (ref "OF2") (pin "1") (pinfunction "1_1") (pintype "bidirectional"))
      (node (ref "XO") (pin "4") (pinfunction "SK_4") (pintype "passive"))
    )
    (net (code "132") (name "Net-(XOF-SK)") (class "Default")
      (node (ref "OF3") (pin "1") (pinfunction "1_1") (pintype "bidirectional"))
      (node (ref "XO") (pin "5") (pinfunction "SK_5") (pintype "passive"))
    )
    (net (code "133") (name "Net-(XOG-SK)") (class "Default")
      (node (ref "OF4") (pin "1") (pinfunction "1_1") (pintype "bidirectional"))
      (node (ref "XO") (pin "6") (pinfunction "SK_6") (pintype "passive"))
    )
    (net (code "134") (name "Net-(XOH-SK)") (class "Default")
      (node (ref "OF5") (pin "1") (pinfunction "1_1") (pintype "bidirectional"))
      (node (ref "XO") (pin "7") (pinfunction "SK_7") (pintype "passive"))
    )
    (net (code "135") (name "Net-(XOI-SK)") (class "Default")
      (node (ref "OF6") (pin "1") (pinfunction "1_1") (pintype "bidirectional"))
      (node (ref "XO") (pin "8") (pinfunction "SK_8") (pintype "passive"))
    )
    (net (code "136") (name "Net-(XOJ-SK)") (class "Default")
      (node (ref "OF7") (pin "1") (pinfunction "1_1") (pintype "bidirectional"))
      (node (ref "XO") (pin "9") (pinfunction "SK_9") (pintype "passive"))
    )
    (net (code "137") (name "OI1") (class "Default")
      (node (ref "OK3") (pin "15") (pinfunction "EMIT_15") (pintype "passive"))
      (node (ref "OR2") (pin "1") (pinfunction "1_1") (pintype "passive"))
      (node (ref "U1") (pin "8") (pinfunction "8B_8") (pintype "input"))
    )
    (net (code "138") (name "OI2") (class "Default")
      (node (ref "OK3") (pin "13") (pinfunction "EMIT_13") (pintype "passive"))
      (node (ref "OR2") (pin "2") (pinfunction "1_2") (pintype "passive"))
      (node (ref "U1") (pin "7") (pinfunction "7B_7") (pintype "input"))
    )
    (net (code "139") (name "OI3") (class "Default")
      (node (ref "OK3") (pin "11") (pinfunction "EMIT_11") (pintype "passive"))
      (node (ref "OR2") (pin "3") (pinfunction "1_3") (pintype "passive"))
      (node (ref "U1") (pin "6") (pinfunction "6B_6") (pintype "input"))
    )
    (net (code "140") (name "OI4") (class "Default")
      (node (ref "OK3") (pin "9") (pinfunction "EMIT_9") (pintype "passive"))
      (node (ref "OR2") (pin "4") (pinfunction "1_4") (pintype "passive"))
      (node (ref "U1") (pin "5") (pinfunction "5B_5") (pintype "input"))
    )
    (net (code "141") (name "RAW_IV") (class "Default")
      (node (ref "GPIO") (pin "1") (pinfunction "S_1") (pintype "passive"))
      (node (ref "PC1") (pin "+") (pinfunction "+_+") (pintype "passive"))
      (node (ref "PF1") (pin "2") (pinfunction "2_2") (pintype "passive"))
      (node (ref "PIC33") (pin "1") (pinfunction "VIN_1") (pintype "input"))
    )
    (net (code "142") (name "RESET") (class "Default")
      (node (ref "BL") (pin "5") (pinfunction "S_5") (pintype "passive"))
      (node (ref "C2") (pin "1") (pinfunction "1_1") (pintype "passive"))
      (node (ref "MC") (pin "29") (pinfunction "PC6(/RESET)_29") (pintype "bidirectional"))
      (node (ref "R2") (pin "1") (pinfunction "1_1") (pintype "passive"))
      (node (ref "SR") (pin "1") (pinfunction "P_1") (pintype "passive"))
    )
    (net (code "143") (name "RXI") (class "Default")
      (node (ref "MC") (pin "30") (pinfunction "PD0(RXD)_30") (pintype "bidirectional"))
      (node (ref "PP") (pin "4") (pinfunction "S_4") (pintype "passive"))
    )
    (net (code "144") (name "TXO") (class "Default")
      (node (ref "MC") (pin "31") (pinfunction "PD1(TXD)_31") (pintype "bidirectional"))
      (node (ref "PP") (pin "3") (pinfunction "S_3") (pintype "passive"))
    )
    (net (code "145") (name "VDDO") (class "Default")
      (node (ref "D1") (pin "3") (pinfunction "3_3") (pintype "bidirectional"))
      (node (ref "D2") (pin "3") (pinfunction "3_3") (pintype "bidirectional"))
      (node (ref "D3") (pin "3") (pinfunction "3_3") (pintype "bidirectional"))
      (node (ref "D4") (pin "3") (pinfunction "3_3") (pintype "bidirectional"))
      (node (ref "EC6") (pin "+") (pinfunction "+_+") (pintype "passive"))
      (node (ref "OD2") (pin "C") (pinfunction "C_C") (pintype "passive"))
      (node (ref "OMF") (pin "1") (pinfunction "1_1") (pintype "bidirectional"))
      (node (ref "OR3") (pin "5") (pinfunction "2_5") (pintype "passive"))
      (node (ref "OR3") (pin "6") (pinfunction "2_6") (pintype "passive"))
      (node (ref "OR3") (pin "7") (pinfunction "2_7") (pintype "passive"))
      (node (ref "OR3") (pin "8") (pinfunction "2_8") (pintype "passive"))
      (node (ref "OR5") (pin "5") (pinfunction "2_5") (pintype "passive"))
      (node (ref "OR5") (pin "6") (pinfunction "2_6") (pintype "passive"))
      (node (ref "OR5") (pin "7") (pinfunction "2_7") (pintype "passive"))
      (node (ref "OR5") (pin "8") (pinfunction "2_8") (pintype "passive"))
      (node (ref "U1") (pin "10") (pinfunction "COM_10") (pintype "output"))
    )
    (net (code "146") (name "VIN") (class "Default")
      (node (ref "PD1") (pin "A") (pinfunction "A_A") (pintype "passive"))
      (node (ref "PJ1") (pin "VIN0") (pinfunction "PWR_VIN0") (pintype "bidirectional"))
      (node (ref "XV") (pin "2") (pinfunction "SK_2") (pintype "passive"))
    )
    (net (code "147") (name "WFGPIO0") (class "Default")
      (node (ref "GPIO") (pin "13") (pinfunction "S_13") (pintype "passive"))
      (node (ref "WIFI") (pin "GPIO0") (pinfunction "GPIO0_GPIO0") (pintype "bidirectional"))
    )
    (net (code "148") (name "WFGPIO2") (class "Default")
      (node (ref "GPIO") (pin "14") (pinfunction "S_14") (pintype "passive"))
      (node (ref "WIFI") (pin "GPIO2") (pinfunction "GPIO2_GPIO2") (pintype "bidirectional"))
    )
    (net (code "149") (name "unconnected-(ENC-CLKOUT-Pad3)") (class "Default")
      (node (ref "ENC") (pin "3") (pinfunction "CLKOUT_3") (pintype "output"))
    )
    (net (code "150") (name "unconnected-(ENC-WOL-Pad5)") (class "Default")
      (node (ref "ENC") (pin "5") (pinfunction "WOL_5") (pintype "output"))
    )
    (net (code "151") (name "unconnected-(IC1-INTA-Pad20)") (class "Default")
      (node (ref "IC1") (pin "20") (pinfunction "INTA_20") (pintype "output"))
    )
    (net (code "152") (name "unconnected-(PJ1-GND-PadP$4)") (class "Default")
      (node (ref "PJ1") (pin "P$4") (pinfunction "GND_P$4") (pintype "bidirectional"))
    )
    (net (code "153") (name "unconnected-(SHT-PadALERT)") (class "Default")
      (node (ref "SHT") (pin "ALERT") (pinfunction "ALERT_ALERT") (pintype "bidirectional"))
    )
    (net (code "154") (name "unconnected-(SHT-PadRESET)") (class "Default")
      (node (ref "SHT") (pin "RESET") (pinfunction "RESET_RESET") (pintype "bidirectional"))
    )
    (net (code "155") (name "unconnected-(U$2-PadNC)") (class "Default")
      (node (ref "U$2") (pin "NC") (pinfunction "NC_NC") (pintype "bidirectional"))
    )
    (net (code "156") (name "unconnected-(WIFI-PadRST)") (class "Default")
      (node (ref "WIFI") (pin "RST") (pinfunction "RST_RST") (pintype "bidirectional"))
    )
  )
)
